# LPCB234_-_CHARGER_IF.net
KiCad netlist of a schematic drawn in Altium Designer
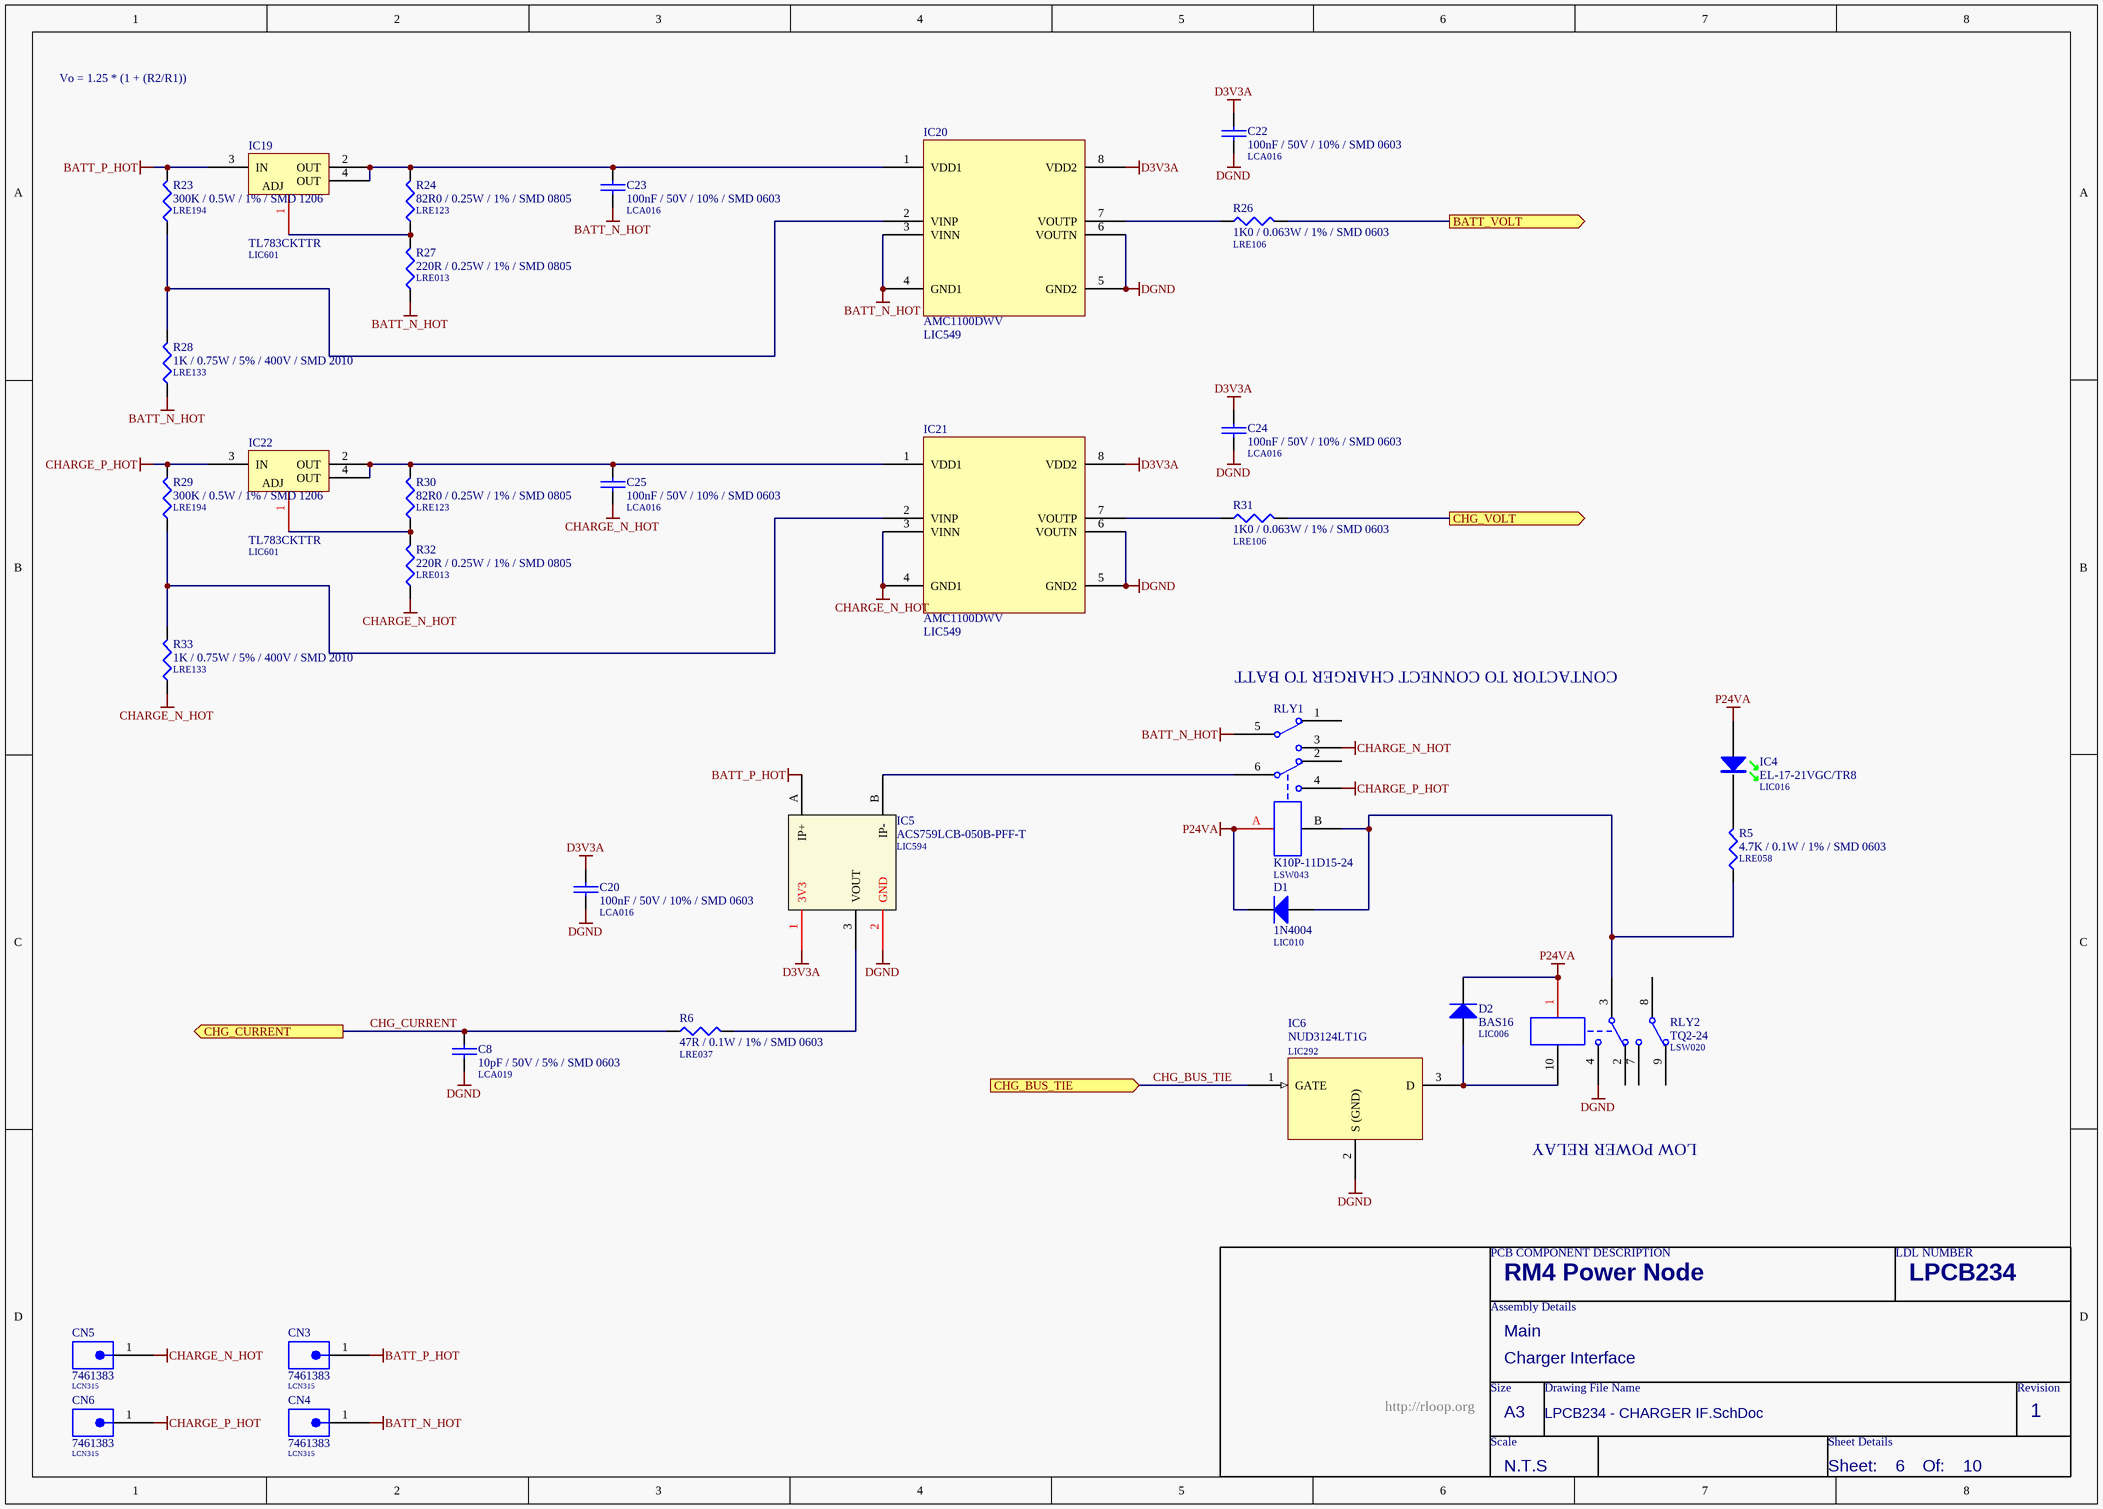
[diagram p0: LPCB234 - CHARGER IF.SchDoc]

(export (version "E")
  (design (tool "Eeschema 10.0.6"))
  (components
    (comp (ref "C8")
      (value "10pF / 50V / 5% / SMD 0603")
      (footprint "LFP011__CC1608-0603-IPC7351_B")
      (description "Capacitor, Ceramic Chip, 10pF, 50V, 5%, SMD 0603 [LCA019]")
      (fields (field (name "LDL_NUMBER") "LCA019"))
      (libsource (lib "LDL_Capacitors") (part "10pF / 50V / 5% / SMD 0603"))
    )
    (comp (ref "C20")
      (value "100nF / 50V / 10% / SMD 0603")
      (footprint "LFP011__CC1608-0603-IPC7351_B")
      (description "Capacitor, Ceramic Chip, 100nF (0.1uF), 50V, 5%, SMD 0603 [LCA016]")
      (fields (field (name "LDL_NUMBER") "LCA016"))
      (libsource (lib "LDL_Capacitors") (part "100nF / 50V / 10% / SMD 0603"))
    )
    (comp (ref "C22")
      (value "100nF / 50V / 10% / SMD 0603")
      (footprint "LFP011__CC1608-0603-IPC7351_B")
      (description "Capacitor, Ceramic Chip, 100nF (0.1uF), 50V, 5%, SMD 0603 [LCA016]")
      (fields (field (name "LDL_NUMBER") "LCA016"))
      (libsource (lib "LDL_Capacitors") (part "100nF / 50V / 10% / SMD 0603"))
    )
    (comp (ref "C23")
      (value "100nF / 50V / 10% / SMD 0603")
      (footprint "LFP011__CC1608-0603-IPC7351_B")
      (description "Capacitor, Ceramic Chip, 100nF (0.1uF), 50V, 5%, SMD 0603 [LCA016]")
      (fields (field (name "LDL_NUMBER") "LCA016"))
      (libsource (lib "LDL_Capacitors") (part "100nF / 50V / 10% / SMD 0603"))
    )
    (comp (ref "C24")
      (value "100nF / 50V / 10% / SMD 0603")
      (footprint "LFP011__CC1608-0603-IPC7351_B")
      (description "Capacitor, Ceramic Chip, 100nF (0.1uF), 50V, 5%, SMD 0603 [LCA016]")
      (fields (field (name "LDL_NUMBER") "LCA016"))
      (libsource (lib "LDL_Capacitors") (part "100nF / 50V / 10% / SMD 0603"))
    )
    (comp (ref "C25")
      (value "100nF / 50V / 10% / SMD 0603")
      (footprint "LFP011__CC1608-0603-IPC7351_B")
      (description "Capacitor, Ceramic Chip, 100nF (0.1uF), 50V, 5%, SMD 0603 [LCA016]")
      (fields (field (name "LDL_NUMBER") "LCA016"))
      (libsource (lib "LDL_Capacitors") (part "100nF / 50V / 10% / SMD 0603"))
    )
    (comp (ref "CN3")
      (value "7461383")
      (footprint "7461383")
      (description "Terminal, Bush with M5 Shank")
      (fields (field (name "LDL_NUMBER") "LCN315"))
      (libsource (lib "LDL_Connectors") (part "7461383"))
    )
    (comp (ref "CN4")
      (value "7461383")
      (footprint "7461383")
      (description "Terminal, Bush with M5 Shank")
      (fields (field (name "LDL_NUMBER") "LCN315"))
      (libsource (lib "LDL_Connectors") (part "7461383"))
    )
    (comp (ref "CN5")
      (value "7461383")
      (footprint "7461383")
      (description "Terminal, Bush with M5 Shank")
      (fields (field (name "LDL_NUMBER") "LCN315"))
      (libsource (lib "LDL_Connectors") (part "7461383"))
    )
    (comp (ref "CN6")
      (value "7461383")
      (footprint "7461383")
      (description "Terminal, Bush with M5 Shank")
      (fields (field (name "LDL_NUMBER") "LCN315"))
      (libsource (lib "LDL_Connectors") (part "7461383"))
    )
    (comp (ref "D1")
      (value "1N4004")
      (footprint "DO-41")
      (description "Diode, General Purpose Rectifier, 1A, PTH [LIC010]")
      (fields (field (name "LDL_NUMBER") "LIC010"))
      (libsource (lib "LDL_Semiconductors") (part "1N4004"))
    )
    (comp (ref "D2")
      (value "BAS16")
      (footprint "LFP021__SOT23")
      (description "Diode, Small Signal, 0.2A, 85V, SMD SOT-23 [LIC006]")
      (fields (field (name "LDL_NUMBER") "LIC006"))
      (libsource (lib "LDL_Semiconductors") (part "BAS16"))
    )
    (comp (ref "IC4")
      (value "EL-17-21VGC/TR8")
      (footprint "CR2012-0805-LED")
      (description "LED, SMD, 0805 Green [LIC016]")
      (fields (field (name "LDL_NUMBER") "LIC016"))
      (libsource (lib "LDL_Semiconductors") (part "EL-17-21VGC/TR8"))
    )
    (comp (ref "IC5")
      (value "ACS759LCB-050B-PFF-T")
      (footprint "CB-PFF")
      (description "IC, Hall Effect Current Sensor, PTH")
      (fields (field (name "LDL_NUMBER") "LIC594"))
      (libsource (lib "LDL_Semiconductors") (part "ACS759LCB-050B-PFF-T"))
    )
    (comp (ref "IC6")
      (value "NUD3124LT1G")
      (footprint "LFP021__SOT23")
      (description "IC, Relay Driver, 28V Industrial, SMD SOT23 [LIC292]")
      (fields (field (name "LDL_NUMBER") "LIC292"))
      (libsource (lib "LDL_Semiconductors") (part "NUD3124LT1G"))
    )
    (comp (ref "IC19")
      (value "TL783CKTTR")
      (footprint "LFP147__KTT-R-PSFM-G3")
      (description "IC, High Volt LDO, 0.7A [LIC601]")
      (fields (field (name "LDL_NUMBER") "LIC601"))
      (libsource (lib "LDL_Semiconductors") (part "TL783CKTTR"))
    )
    (comp (ref "IC20")
      (value "AMC1100DWV")
      (footprint "LFP116__R-PDSO-G8")
      (description "IC, Isolation Amplifier, SMD SOIC8 [LIC549]")
      (fields (field (name "LDL_NUMBER") "LIC549"))
      (libsource (lib "LDL_Semiconductors") (part "AMC1100DWV"))
    )
    (comp (ref "IC21")
      (value "AMC1100DWV")
      (footprint "LFP116__R-PDSO-G8")
      (description "IC, Isolation Amplifier, SMD SOIC8 [LIC549]")
      (fields (field (name "LDL_NUMBER") "LIC549"))
      (libsource (lib "LDL_Semiconductors") (part "AMC1100DWV"))
    )
    (comp (ref "IC22")
      (value "TL783CKTTR")
      (footprint "LFP147__KTT-R-PSFM-G3")
      (description "IC, High Volt LDO, 0.7A [LIC601]")
      (fields (field (name "LDL_NUMBER") "LIC601"))
      (libsource (lib "LDL_Semiconductors") (part "TL783CKTTR"))
    )
    (comp (ref "R5")
      (value "4.7K / 0.1W / 1% / SMD 0603")
      (footprint "LFP020__CR1608-0603-IPC7351_B")
      (description "Resistor, Ceramic Chip, 4K7, 0.1W, 1%, SMD 0603 [LRE058]")
      (fields (field (name "LDL_NUMBER") "LRE058"))
      (libsource (lib "LDL_Resistors") (part "4.7K / 0.1W / 1% / SMD 0603"))
    )
    (comp (ref "R6")
      (value "47R / 0.1W / 1% / SMD 0603")
      (footprint "LFP020__CR1608-0603-IPC7351_B")
      (description "Resistor, Ceramic Chip, 47R, 0.1W, 1%, SMD 0603 [LRE037]")
      (fields (field (name "LDL_NUMBER") "LRE037"))
      (libsource (lib "LDL_Resistors") (part "47R / 0.1W / 1% / SMD 0603"))
    )
    (comp (ref "R23")
      (value "300K / 0.5W / 1% / SMD 1206")
      (footprint "LFP107__CR3216-1206")
      (description "Resistor, Thick Film, 300K, 0.500W, 200V, 1%, SMD 1206 [LRE194]")
      (fields (field (name "LDL_NUMBER") "LRE194"))
      (libsource (lib "LDL_Resistors") (part "300K / 0.5W / 1% / SMD 1206"))
    )
    (comp (ref "R24")
      (value "82R0 / 0.25W / 1% / SMD 0805")
      (footprint "LFP029__CR2012-0805")
      (description "Resistor, Ceramic Chip, 82R, 0.063W, 1%, SMD 0805 [LRE123]")
      (fields (field (name "LDL_NUMBER") "LRE123"))
      (libsource (lib "LDL_Resistors") (part "82R0 / 0.25W / 1% / SMD 0805"))
    )
    (comp (ref "R26")
      (value "1K0 / 0.063W / 1% / SMD 0603")
      (footprint "LFP020__CR1608-0603-IPC7351_B")
      (description "Resistor, Ceramic Chip, 1K0, 0.063W, 1%, SMD 0603 [LRE106]")
      (fields (field (name "LDL_NUMBER") "LRE106"))
      (libsource (lib "LDL_Resistors") (part "1K0 / 0.063W / 1% / SMD 0603"))
    )
    (comp (ref "R27")
      (value "220R / 0.25W / 1% / SMD 0805")
      (footprint "LFP029__CR2012-0805")
      (description "Resistor, Ceramic Chip, 220R, 0.25W, 1%, SMD 0805 [LRE013]")
      (fields (field (name "LDL_NUMBER") "LRE013"))
      (libsource (lib "LDL_Resistors") (part "220R / 0.25W / 1% / SMD 0805"))
    )
    (comp (ref "R28")
      (value "1K / 0.75W / 5% / 400V / SMD 2010")
      (footprint "LFP060__CR5025-2010")
      (description "Resistor, Thick Film, 1K, 0.75W, 5%, 400V, SMD 2010 [LRE133]")
      (fields (field (name "LDL_NUMBER") "LRE133"))
      (libsource (lib "LDL_Resistors") (part "1K / 0.75W / 5% / 400V / SMD 2010"))
    )
    (comp (ref "R29")
      (value "300K / 0.5W / 1% / SMD 1206")
      (footprint "LFP107__CR3216-1206")
      (description "Resistor, Thick Film, 300K, 0.500W, 200V, 1%, SMD 1206 [LRE194]")
      (fields (field (name "LDL_NUMBER") "LRE194"))
      (libsource (lib "LDL_Resistors") (part "300K / 0.5W / 1% / SMD 1206"))
    )
    (comp (ref "R30")
      (value "82R0 / 0.25W / 1% / SMD 0805")
      (footprint "LFP029__CR2012-0805")
      (description "Resistor, Ceramic Chip, 82R, 0.063W, 1%, SMD 0805 [LRE123]")
      (fields (field (name "LDL_NUMBER") "LRE123"))
      (libsource (lib "LDL_Resistors") (part "82R0 / 0.25W / 1% / SMD 0805"))
    )
    (comp (ref "R31")
      (value "1K0 / 0.063W / 1% / SMD 0603")
      (footprint "LFP020__CR1608-0603-IPC7351_B")
      (description "Resistor, Ceramic Chip, 1K0, 0.063W, 1%, SMD 0603 [LRE106]")
      (fields (field (name "LDL_NUMBER") "LRE106"))
      (libsource (lib "LDL_Resistors") (part "1K0 / 0.063W / 1% / SMD 0603"))
    )
    (comp (ref "R32")
      (value "220R / 0.25W / 1% / SMD 0805")
      (footprint "LFP029__CR2012-0805")
      (description "Resistor, Ceramic Chip, 220R, 0.25W, 1%, SMD 0805 [LRE013]")
      (fields (field (name "LDL_NUMBER") "LRE013"))
      (libsource (lib "LDL_Resistors") (part "220R / 0.25W / 1% / SMD 0805"))
    )
    (comp (ref "R33")
      (value "1K / 0.75W / 5% / 400V / SMD 2010")
      (footprint "LFP060__CR5025-2010")
      (description "Resistor, Thick Film, 1K, 0.75W, 5%, 400V, SMD 2010 [LRE133]")
      (fields (field (name "LDL_NUMBER") "LRE133"))
      (libsource (lib "LDL_Resistors") (part "1K / 0.75W / 5% / 400V / SMD 2010"))
    )
    (comp (ref "RLY1")
      (value "K10P-11D15-24")
      (footprint "K10P-11D15-24")
      (description "Relay, DPDT, 24V, Socket Mount")
      (fields (field (name "LDL_NUMBER") "LSW043"))
      (libsource (lib "LDL_Switching") (part "K10P-11D15-24"))
    )
    (comp (ref "RLY2")
      (value "TQ2-24")
      (footprint "TQ2")
      (description "Relay, DPDT, Non Latching, 24VDC Coil, 1A Rating, PTH")
      (fields (field (name "LDL_NUMBER") "LSW020"))
      (libsource (lib "LDL_Switching") (part "TQ2-24"))
    )
  )
  (nets
    (net (code "1") (name "/BATT_VOLT") (class "Default") (node (ref "R26") (pin "2") (pintype "passive")))
    (net (code "2") (name "/CHG_BUS_TIE") (class "Default")
      (node (ref "IC6") (pin "1") (pinfunction "GATE_1") (pintype "input"))
    )
    (net (code "3") (name "/CHG_CURRENT") (class "Default")
      (node (ref "C8") (pin "1") (pintype "passive"))
      (node (ref "R6") (pin "1") (pintype "passive"))
    )
    (net (code "4") (name "/CHG_VOLT") (class "Default") (node (ref "R31") (pin "2") (pintype "passive")))
    (net (code "5") (name "BATT_N_HOT") (class "Default")
      (node (ref "C23") (pin "2") (pintype "passive"))
      (node (ref "CN4") (pin "1") (pinfunction "1_1") (pintype "passive"))
      (node (ref "IC20") (pin "3") (pinfunction "VINN_3") (pintype "passive"))
      (node (ref "IC20") (pin "4") (pinfunction "GND1_4") (pintype "power_in"))
      (node (ref "R27") (pin "1") (pintype "passive"))
      (node (ref "R28") (pin "1") (pintype "passive"))
      (node (ref "RLY1") (pin "5") (pinfunction "5_5") (pintype "passive"))
    )
    (net (code "6") (name "BATT_P_HOT") (class "Default")
      (node (ref "CN3") (pin "1") (pinfunction "1_1") (pintype "passive"))
      (node (ref "IC19") (pin "3") (pinfunction "IN_3") (pintype "power_in"))
      (node (ref "IC5") (pin "A") (pinfunction "IP+_A") (pintype "passive"))
      (node (ref "R23") (pin "2") (pintype "passive"))
    )
    (net (code "7") (name "CHARGE_N_HOT") (class "Default")
      (node (ref "C25") (pin "2") (pintype "passive"))
      (node (ref "CN5") (pin "1") (pinfunction "1_1") (pintype "passive"))
      (node (ref "IC21") (pin "3") (pinfunction "VINN_3") (pintype "passive"))
      (node (ref "IC21") (pin "4") (pinfunction "GND1_4") (pintype "power_in"))
      (node (ref "R32") (pin "1") (pintype "passive"))
      (node (ref "R33") (pin "1") (pintype "passive"))
      (node (ref "RLY1") (pin "3") (pinfunction "3_3") (pintype "passive"))
    )
    (net (code "8") (name "CHARGE_P_HOT") (class "Default")
      (node (ref "CN6") (pin "1") (pinfunction "1_1") (pintype "passive"))
      (node (ref "IC22") (pin "3") (pinfunction "IN_3") (pintype "power_in"))
      (node (ref "R29") (pin "2") (pintype "passive"))
      (node (ref "RLY1") (pin "4") (pinfunction "4_4") (pintype "passive"))
    )
    (net (code "9") (name "D3V3A") (class "Default")
      (node (ref "C20") (pin "1") (pintype "passive"))
      (node (ref "C22") (pin "1") (pintype "passive"))
      (node (ref "C24") (pin "1") (pintype "passive"))
      (node (ref "IC20") (pin "8") (pinfunction "VDD2_8") (pintype "power_in"))
      (node (ref "IC21") (pin "8") (pinfunction "VDD2_8") (pintype "power_in"))
      (node (ref "IC5") (pin "1") (pinfunction "3V3_1") (pintype "power_in"))
    )
    (net (code "10") (name "DGND") (class "Default")
      (node (ref "C20") (pin "2") (pintype "passive"))
      (node (ref "C22") (pin "2") (pintype "passive"))
      (node (ref "C24") (pin "2") (pintype "passive"))
      (node (ref "C8") (pin "2") (pintype "passive"))
      (node (ref "IC20") (pin "5") (pinfunction "GND2_5") (pintype "power_in"))
      (node (ref "IC20") (pin "6") (pinfunction "VOUTN_6") (pintype "passive"))
      (node (ref "IC21") (pin "5") (pinfunction "GND2_5") (pintype "power_in"))
      (node (ref "IC21") (pin "6") (pinfunction "VOUTN_6") (pintype "passive"))
      (node (ref "IC5") (pin "2") (pinfunction "GND_2") (pintype "power_in"))
      (node (ref "IC6") (pin "2") (pinfunction "S_(GND)_2") (pintype "passive"))
      (node (ref "RLY2") (pin "4") (pinfunction "4_4") (pintype "passive"))
    )
    (net (code "11") (name "Net-(D1-PadA)") (class "Default")
      (node (ref "D1") (pin "A") (pinfunction "A_A") (pintype "passive"))
      (node (ref "R5") (pin "1") (pintype "passive"))
      (node (ref "RLY1") (pin "B") (pinfunction "B_B") (pintype "passive"))
      (node (ref "RLY2") (pin "3") (pinfunction "3_3") (pintype "passive"))
    )
    (net (code "12") (name "Net-(D2-A)") (class "Default")
      (node (ref "D2") (pin "1") (pinfunction "A_1") (pintype "passive"))
      (node (ref "IC6") (pin "3") (pinfunction "D_3") (pintype "passive"))
      (node (ref "RLY2") (pin "10") (pinfunction "10_10") (pintype "passive"))
    )
    (net (code "13") (name "Net-(IC4-PadK)") (class "Default")
      (node (ref "IC4") (pin "K") (pintype "passive"))
      (node (ref "R5") (pin "2") (pintype "passive"))
    )
    (net (code "14") (name "Net-(IC5-IP-)") (class "Default")
      (node (ref "IC5") (pin "B") (pinfunction "IP-_B") (pintype "passive"))
      (node (ref "RLY1") (pin "6") (pinfunction "6_6") (pintype "passive"))
    )
    (net (code "15") (name "Net-(IC5-VOUT)") (class "Default")
      (node (ref "IC5") (pin "3") (pinfunction "VOUT_3") (pintype "passive"))
      (node (ref "R6") (pin "2") (pintype "passive"))
    )
    (net (code "16") (name "Net-(IC19-ADJ)") (class "Default")
      (node (ref "IC19") (pin "1") (pinfunction "ADJ_1") (pintype "power_in"))
      (node (ref "R24") (pin "1") (pintype "passive"))
      (node (ref "R27") (pin "2") (pintype "passive"))
    )
    (net (code "17") (name "Net-(IC20-VDD1)") (class "Default")
      (node (ref "C23") (pin "1") (pintype "passive"))
      (node (ref "IC19") (pin "2") (pinfunction "OUT_2") (pintype "power_in"))
      (node (ref "IC19") (pin "4") (pinfunction "OUT_4") (pintype "power_in"))
      (node (ref "IC20") (pin "1") (pinfunction "VDD1_1") (pintype "power_in"))
      (node (ref "R24") (pin "2") (pintype "passive"))
    )
    (net (code "18") (name "Net-(IC20-VINP)") (class "Default")
      (node (ref "IC20") (pin "2") (pinfunction "VINP_2") (pintype "passive"))
      (node (ref "R23") (pin "1") (pintype "passive"))
      (node (ref "R28") (pin "2") (pintype "passive"))
    )
    (net (code "19") (name "Net-(IC20-VOUTP)") (class "Default")
      (node (ref "IC20") (pin "7") (pinfunction "VOUTP_7") (pintype "passive"))
      (node (ref "R26") (pin "1") (pintype "passive"))
    )
    (net (code "20") (name "Net-(IC21-VDD1)") (class "Default")
      (node (ref "C25") (pin "1") (pintype "passive"))
      (node (ref "IC21") (pin "1") (pinfunction "VDD1_1") (pintype "power_in"))
      (node (ref "IC22") (pin "2") (pinfunction "OUT_2") (pintype "power_in"))
      (node (ref "IC22") (pin "4") (pinfunction "OUT_4") (pintype "power_in"))
      (node (ref "R30") (pin "2") (pintype "passive"))
    )
    (net (code "21") (name "Net-(IC21-VINP)") (class "Default")
      (node (ref "IC21") (pin "2") (pinfunction "VINP_2") (pintype "passive"))
      (node (ref "R29") (pin "1") (pintype "passive"))
      (node (ref "R33") (pin "2") (pintype "passive"))
    )
    (net (code "22") (name "Net-(IC21-VOUTP)") (class "Default")
      (node (ref "IC21") (pin "7") (pinfunction "VOUTP_7") (pintype "passive"))
      (node (ref "R31") (pin "1") (pintype "passive"))
    )
    (net (code "23") (name "Net-(IC22-ADJ)") (class "Default")
      (node (ref "IC22") (pin "1") (pinfunction "ADJ_1") (pintype "power_in"))
      (node (ref "R30") (pin "1") (pintype "passive"))
      (node (ref "R32") (pin "2") (pintype "passive"))
    )
    (net (code "24") (name "P24VA") (class "Default")
      (node (ref "D1") (pin "K") (pinfunction "K_K") (pintype "passive"))
      (node (ref "D2") (pin "3") (pinfunction "K_3") (pintype "passive"))
      (node (ref "IC4") (pin "A") (pintype "passive"))
      (node (ref "RLY1") (pin "A") (pinfunction "A_A") (pintype "passive"))
      (node (ref "RLY2") (pin "1") (pinfunction "1_1") (pintype "passive"))
    )
    (net (code "25") (name "unconnected-(RLY1-Pad1)") (class "Default")
      (node (ref "RLY1") (pin "1") (pinfunction "1_1") (pintype "passive"))
    )
    (net (code "26") (name "unconnected-(RLY1-Pad2)") (class "Default")
      (node (ref "RLY1") (pin "2") (pinfunction "2_2") (pintype "passive"))
    )
    (net (code "27") (name "unconnected-(RLY2-Pad2)") (class "Default")
      (node (ref "RLY2") (pin "2") (pinfunction "2_2") (pintype "passive"))
    )
    (net (code "28") (name "unconnected-(RLY2-Pad7)") (class "Default")
      (node (ref "RLY2") (pin "7") (pinfunction "7_7") (pintype "passive"))
    )
    (net (code "29") (name "unconnected-(RLY2-Pad8)") (class "Default")
      (node (ref "RLY2") (pin "8") (pinfunction "8_8") (pintype "passive"))
    )
    (net (code "30") (name "unconnected-(RLY2-Pad9)") (class "Default")
      (node (ref "RLY2") (pin "9") (pinfunction "9_9") (pintype "passive"))
    )
  )
)
